# L6924D013TR.net
KiCad netlist of a schematic drawn in Altium Designer
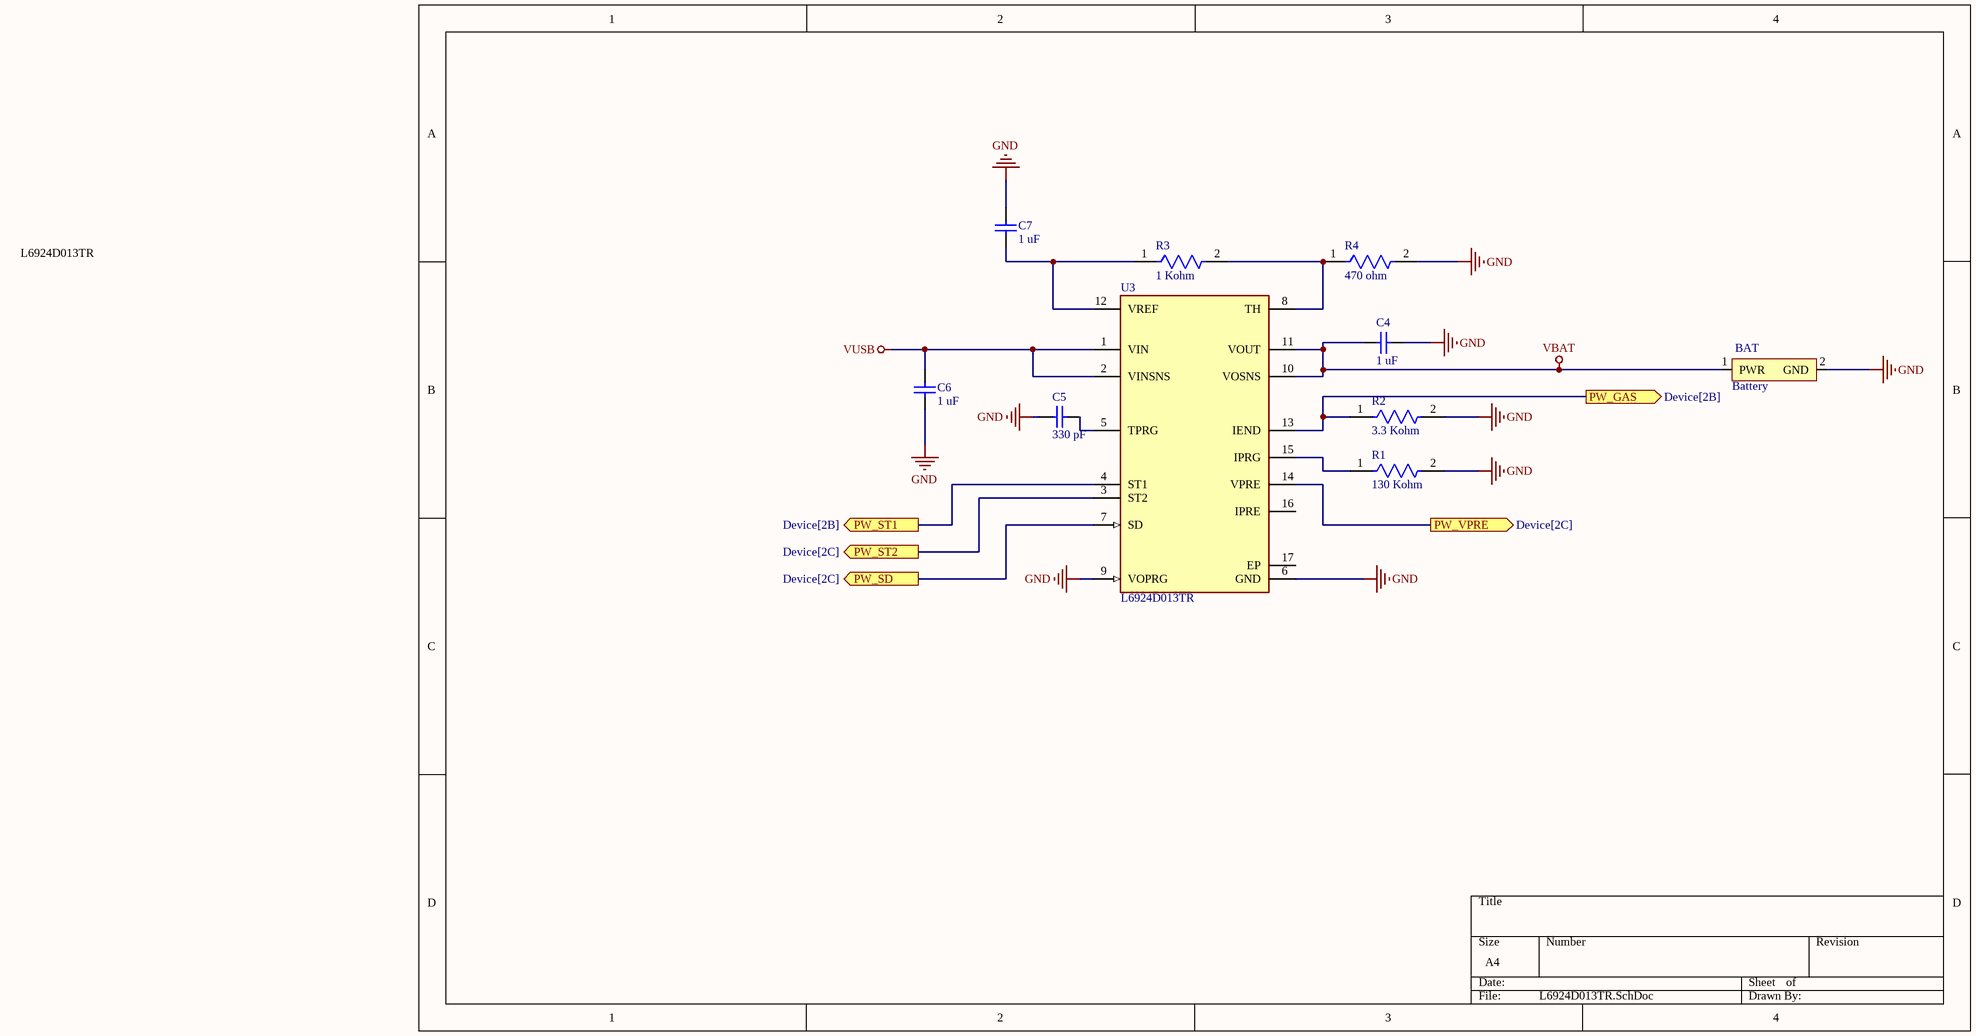
[diagram p0: L6924D013TR.SchDoc]

(export (version "E")
  (design (tool "Eeschema 10.0.6"))
  (components
    (comp (ref "BAT") (value "Battery") (footprint "Battery") (libsource (lib "ANT") (part "Battery")))
    (comp (ref "C4")
      (value "1 uF")
      (footprint "CAPC1005X55X25NL05T10")
      (fields (field (name "MANUFACTURER") "Murata") (field (name "PART NUMBER") "GRM155F50J684ZE01D"))
      (libsource (lib "Altium Content Vault") (part "CAP"))
    )
    (comp (ref "C5")
      (value "330 pF")
      (footprint "CAPC1005X55X25NL05T10")
      (fields (field (name "MANUFACTURER") "Murata") (field (name "PART NUMBER") "GRM155F50J684ZE01D"))
      (libsource (lib "Altium Content Vault") (part "CAP"))
    )
    (comp (ref "C6")
      (value "1 uF")
      (footprint "CAPC1005X55X25NL05T10")
      (fields (field (name "MANUFACTURER") "Murata") (field (name "PART NUMBER") "GRM155F50J684ZE01D"))
      (libsource (lib "Altium Content Vault") (part "CAP"))
    )
    (comp (ref "C7")
      (value "1 uF")
      (footprint "CAPC1005X55X25NL05T10")
      (fields (field (name "MANUFACTURER") "Murata") (field (name "PART NUMBER") "GRM155F50J684ZE01D"))
      (libsource (lib "Altium Content Vault") (part "CAP"))
    )
    (comp (ref "R1")
      (value "130 Kohm")
      (footprint "FP-RC1005-IPC_C")
      (description "Res Thick Film 0402 1.87kΩ 1% 0.063W ±100ppm/°C Molded SMD T/R")
      (fields (field (name "TOLERANCE") "1%"))
      (libsource (lib "Altium Content Vault") (part "1029c3af85768c4190bb7ad29bc67b5"))
    )
    (comp (ref "R2")
      (value "3.3 Kohm")
      (footprint "FP-RC1005-IPC_C")
      (description "Res Thick Film 0402 1.87kΩ 1% 0.063W ±100ppm/°C Molded SMD T/R")
      (fields (field (name "TOLERANCE") "1%"))
      (libsource (lib "Altium Content Vault") (part "1029c3af85768c4190bb7ad29bc67b5"))
    )
    (comp (ref "R3")
      (value "1 Kohm")
      (footprint "FP-RC1005-IPC_C")
      (description "Res Thick Film 0402 1.87kΩ 1% 0.063W ±100ppm/°C Molded SMD T/R")
      (fields (field (name "TOLERANCE") "1%"))
      (libsource (lib "Altium Content Vault") (part "1029c3af85768c4190bb7ad29bc67b5"))
    )
    (comp (ref "R4")
      (value "470 ohm")
      (footprint "FP-RC1005-IPC_C")
      (description "Res Thick Film 0402 1.87kΩ 1% 0.063W ±100ppm/°C Molded SMD T/R")
      (fields (field (name "TOLERANCE") "1%"))
      (libsource (lib "Altium Content Vault") (part "1029c3af85768c4190bb7ad29bc67b5"))
    )
    (comp (ref "U3")
      (value "L6924D013TR")
      (footprint "FP-VFQFPN16-7185330-MFG")
      (description "IC BATT CHRGR ION/POLY 16-VFQFPN")
      (fields
        (field (name "MANUFACTURER") "STMicroelectronics")
        (field (name "OCTOPART") "https://octopart.com/l6924d013tr-stmicroelectronics-421996")
      )
      (libsource (lib "Altium Content Vault") (part "9d43d87a5afbec7d73754d684d84cb7"))
    )
  )
  (nets
    (net (code "1") (name "/PW_GAS") (class "Default")
      (node (ref "R2") (pin "1") (pinfunction "1_1") (pintype "passive"))
      (node (ref "U3") (pin "13") (pinfunction "IEND_13") (pintype "passive"))
    )
    (net (code "2") (name "/PW_SD") (class "Default")
      (node (ref "U3") (pin "7") (pinfunction "SD_7") (pintype "input"))
    )
    (net (code "3") (name "/PW_ST1") (class "Default")
      (node (ref "U3") (pin "4") (pinfunction "ST1_4") (pintype "open_collector"))
    )
    (net (code "4") (name "/PW_ST2") (class "Default")
      (node (ref "U3") (pin "3") (pinfunction "ST2_3") (pintype "open_collector"))
    )
    (net (code "5") (name "/PW_VPRE") (class "Default")
      (node (ref "U3") (pin "14") (pinfunction "VPRE_14") (pintype "passive"))
    )
    (net (code "6") (name "GND") (class "Default")
      (node (ref "BAT") (pin "2") (pinfunction "GND_2") (pintype "power_in"))
      (node (ref "C4") (pin "1") (pinfunction "1_1") (pintype "passive"))
      (node (ref "C5") (pin "2") (pinfunction "2_2") (pintype "passive"))
      (node (ref "C6") (pin "2") (pinfunction "2_2") (pintype "passive"))
      (node (ref "C7") (pin "1") (pinfunction "1_1") (pintype "passive"))
      (node (ref "R1") (pin "2") (pinfunction "2_2") (pintype "passive"))
      (node (ref "R2") (pin "2") (pinfunction "2_2") (pintype "passive"))
      (node (ref "R4") (pin "2") (pinfunction "2_2") (pintype "passive"))
      (node (ref "U3") (pin "6") (pinfunction "GND_6") (pintype "power_in"))
      (node (ref "U3") (pin "9") (pinfunction "VOPRG_9") (pintype "input"))
    )
    (net (code "7") (name "Net-(U3-IPRG)") (class "Default")
      (node (ref "R1") (pin "1") (pinfunction "1_1") (pintype "passive"))
      (node (ref "U3") (pin "15") (pinfunction "IPRG_15") (pintype "passive"))
    )
    (net (code "8") (name "Net-(U3-TH)") (class "Default")
      (node (ref "R3") (pin "2") (pinfunction "2_2") (pintype "passive"))
      (node (ref "R4") (pin "1") (pinfunction "1_1") (pintype "passive"))
      (node (ref "U3") (pin "8") (pinfunction "TH_8") (pintype "passive"))
    )
    (net (code "9") (name "Net-(U3-TPRG)") (class "Default")
      (node (ref "C5") (pin "1") (pinfunction "1_1") (pintype "passive"))
      (node (ref "U3") (pin "5") (pinfunction "TPRG_5") (pintype "passive"))
    )
    (net (code "10") (name "Net-(U3-VREF)") (class "Default")
      (node (ref "C7") (pin "2") (pinfunction "2_2") (pintype "passive"))
      (node (ref "R3") (pin "1") (pinfunction "1_1") (pintype "passive"))
      (node (ref "U3") (pin "12") (pinfunction "VREF_12") (pintype "power_in"))
    )
    (net (code "11") (name "VBAT") (class "Default")
      (node (ref "BAT") (pin "1") (pinfunction "PWR_1") (pintype "power_in"))
      (node (ref "C4") (pin "2") (pinfunction "2_2") (pintype "passive"))
      (node (ref "U3") (pin "10") (pinfunction "VOSNS_10") (pintype "passive"))
      (node (ref "U3") (pin "11") (pinfunction "VOUT_11") (pintype "power_in"))
    )
    (net (code "12") (name "VUSB") (class "Default")
      (node (ref "C6") (pin "1") (pinfunction "1_1") (pintype "passive"))
      (node (ref "U3") (pin "1") (pinfunction "VIN_1") (pintype "power_in"))
      (node (ref "U3") (pin "2") (pinfunction "VINSNS_2") (pintype "power_in"))
    )
    (net (code "13") (name "unconnected-(U3-EP-Pad17)") (class "Default")
      (node (ref "U3") (pin "17") (pinfunction "EP_17") (pintype "power_in"))
    )
    (net (code "14") (name "unconnected-(U3-IPRE-Pad16)") (class "Default")
      (node (ref "U3") (pin "16") (pinfunction "IPRE_16") (pintype "passive"))
    )
  )
)
